# n64rgb.net
KiCad netlist of a schematic drawn in EAGLE
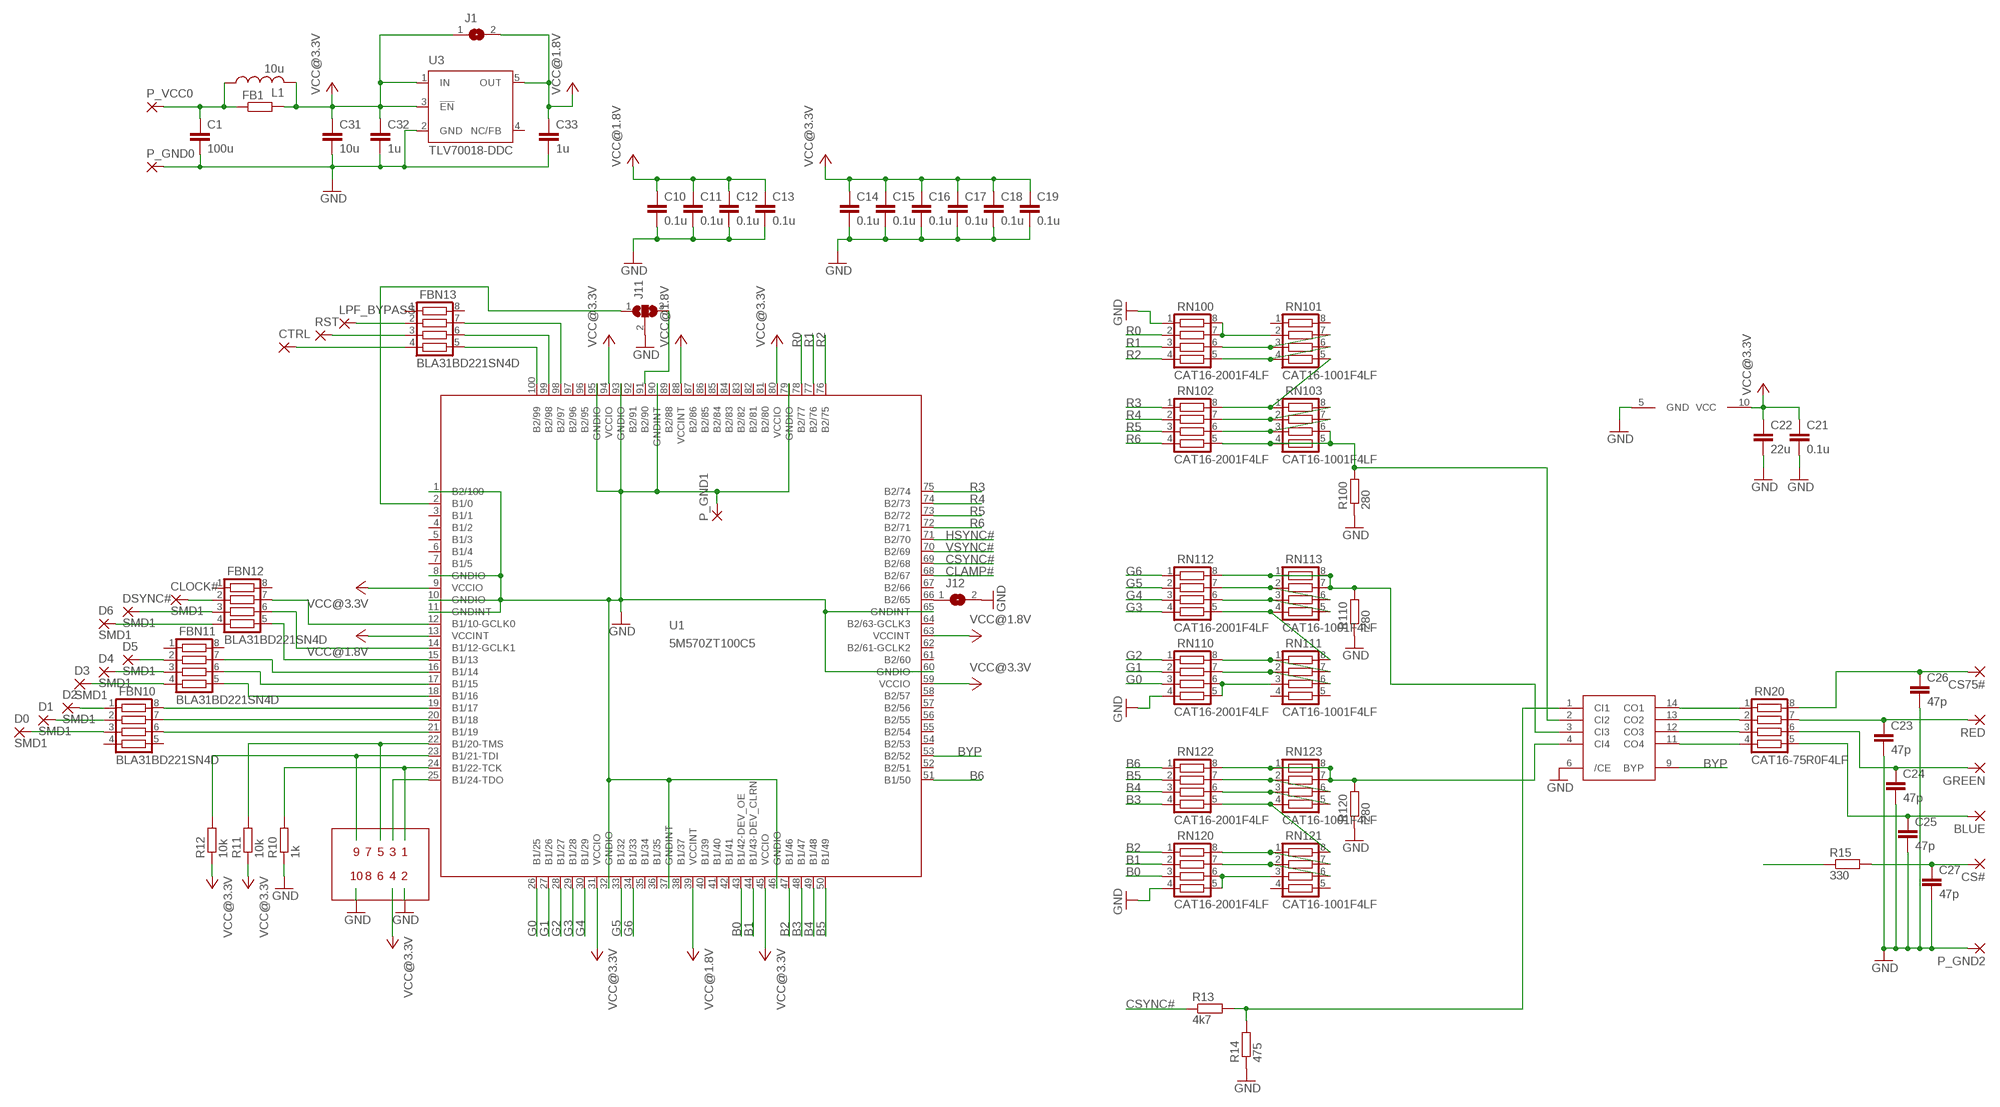
[diagram p0: schematic, sheet 1]

(export (version "E")
  (design (tool "Eeschema 10.0.6"))
  (components
    (comp (ref "BLUE")
      (value "SMD2")
      (footprint "eagle-import:SMD1,27-2,54")
      (libsource (lib "eagle-import") (part "SMD2"))
    )
    (comp (ref "C1")
      (value "100u")
      (footprint "eagle-import:C1206K")
      (libsource (lib "eagle-import") (part "C-EUC1206K"))
    )
    (comp (ref "C10")
      (value "0.1u")
      (footprint "eagle-import:C0603")
      (libsource (lib "eagle-import") (part "C-EUC0603"))
    )
    (comp (ref "C11")
      (value "0.1u")
      (footprint "eagle-import:C0603")
      (libsource (lib "eagle-import") (part "C-EUC0603"))
    )
    (comp (ref "C12")
      (value "0.1u")
      (footprint "eagle-import:C0603")
      (libsource (lib "eagle-import") (part "C-EUC0603"))
    )
    (comp (ref "C13")
      (value "0.1u")
      (footprint "eagle-import:C0603")
      (libsource (lib "eagle-import") (part "C-EUC0603"))
    )
    (comp (ref "C14")
      (value "0.1u")
      (footprint "eagle-import:C0603")
      (libsource (lib "eagle-import") (part "C-EUC0603"))
    )
    (comp (ref "C15")
      (value "0.1u")
      (footprint "eagle-import:C0603")
      (libsource (lib "eagle-import") (part "C-EUC0603"))
    )
    (comp (ref "C16")
      (value "0.1u")
      (footprint "eagle-import:C0603")
      (libsource (lib "eagle-import") (part "C-EUC0603"))
    )
    (comp (ref "C17")
      (value "0.1u")
      (footprint "eagle-import:C0603")
      (libsource (lib "eagle-import") (part "C-EUC0603"))
    )
    (comp (ref "C18")
      (value "0.1u")
      (footprint "eagle-import:C0603")
      (libsource (lib "eagle-import") (part "C-EUC0603"))
    )
    (comp (ref "C19")
      (value "0.1u")
      (footprint "eagle-import:C0603")
      (libsource (lib "eagle-import") (part "C-EUC0603"))
    )
    (comp (ref "C21")
      (value "0.1u")
      (footprint "eagle-import:C0603")
      (libsource (lib "eagle-import") (part "C-EUC0603"))
    )
    (comp (ref "C22")
      (value "22u")
      (footprint "eagle-import:C1206K")
      (libsource (lib "eagle-import") (part "C-EUC1206K"))
    )
    (comp (ref "C23")
      (value "47p")
      (footprint "eagle-import:C0603")
      (libsource (lib "eagle-import") (part "C-EUC0603"))
    )
    (comp (ref "C24")
      (value "47p")
      (footprint "eagle-import:C0603")
      (libsource (lib "eagle-import") (part "C-EUC0603"))
    )
    (comp (ref "C25")
      (value "47p")
      (footprint "eagle-import:C0603")
      (libsource (lib "eagle-import") (part "C-EUC0603"))
    )
    (comp (ref "C26")
      (value "47p")
      (footprint "eagle-import:C0603")
      (libsource (lib "eagle-import") (part "C-EUC0603"))
    )
    (comp (ref "C27")
      (value "47p")
      (footprint "eagle-import:C0603")
      (libsource (lib "eagle-import") (part "C-EUC0603"))
    )
    (comp (ref "C31")
      (value "10u")
      (footprint "eagle-import:C1206K")
      (libsource (lib "eagle-import") (part "C-EUC1206K"))
    )
    (comp (ref "C32")
      (value "1u")
      (footprint "eagle-import:C0603")
      (libsource (lib "eagle-import") (part "C-EUC0603"))
    )
    (comp (ref "C33")
      (value "1u")
      (footprint "eagle-import:C0603")
      (libsource (lib "eagle-import") (part "C-EUC0603"))
    )
    (comp (ref "CLOCK#")
      (value "SMD1")
      (footprint "eagle-import:SMD0,8-1,6")
      (libsource (lib "eagle-import") (part "SMD1"))
    )
    (comp (ref "CS#")
      (value "SMD2")
      (footprint "eagle-import:SMD1,27-2,54")
      (libsource (lib "eagle-import") (part "SMD2"))
    )
    (comp (ref "CS75#")
      (value "SMD2")
      (footprint "eagle-import:SMD1,27-2,54")
      (libsource (lib "eagle-import") (part "SMD2"))
    )
    (comp (ref "CTRL")
      (value "SMD2")
      (footprint "eagle-import:SMD1,27-2,54")
      (libsource (lib "eagle-import") (part "SMD2"))
    )
    (comp (ref "D0")
      (value "SMD1")
      (footprint "eagle-import:SMD0,8-1,6")
      (libsource (lib "eagle-import") (part "SMD1"))
    )
    (comp (ref "D1")
      (value "SMD1")
      (footprint "eagle-import:SMD0,8-1,6")
      (libsource (lib "eagle-import") (part "SMD1"))
    )
    (comp (ref "D2")
      (value "SMD1")
      (footprint "eagle-import:SMD0,8-1,6")
      (libsource (lib "eagle-import") (part "SMD1"))
    )
    (comp (ref "D3")
      (value "SMD1")
      (footprint "eagle-import:SMD0,8-1,6")
      (libsource (lib "eagle-import") (part "SMD1"))
    )
    (comp (ref "D4")
      (value "SMD1")
      (footprint "eagle-import:SMD0,8-1,6")
      (libsource (lib "eagle-import") (part "SMD1"))
    )
    (comp (ref "D5")
      (value "SMD1")
      (footprint "eagle-import:SMD0,8-1,6")
      (libsource (lib "eagle-import") (part "SMD1"))
    )
    (comp (ref "D6")
      (value "SMD1")
      (footprint "eagle-import:SMD0,8-1,6")
      (libsource (lib "eagle-import") (part "SMD1"))
    )
    (comp (ref "DSYNC#")
      (value "SMD1")
      (footprint "eagle-import:SMD0,8-1,6")
      (libsource (lib "eagle-import") (part "SMD1"))
    )
    (comp (ref "FB1")
      (value "R-EU_R0603")
      (footprint "eagle-import:R0603")
      (libsource (lib "eagle-import") (part "R-EU_R0603"))
    )
    (comp (ref "FBN10")
      (value "BLA31BD221SN4D")
      (footprint "eagle-import:CTS742C083")
      (libsource (lib "eagle-import") (part "CTS742C083"))
    )
    (comp (ref "FBN11")
      (value "BLA31BD221SN4D")
      (footprint "eagle-import:CTS742C083")
      (libsource (lib "eagle-import") (part "CTS742C083"))
    )
    (comp (ref "FBN12")
      (value "BLA31BD221SN4D")
      (footprint "eagle-import:CTS742C083")
      (libsource (lib "eagle-import") (part "CTS742C083"))
    )
    (comp (ref "FBN13")
      (value "BLA31BD221SN4D")
      (footprint "eagle-import:CTS742C083")
      (libsource (lib "eagle-import") (part "CTS742C083"))
    )
    (comp (ref "GREEN")
      (value "SMD2")
      (footprint "eagle-import:SMD1,27-2,54")
      (libsource (lib "eagle-import") (part "SMD2"))
    )
    (comp (ref "J1") (value "SJ") (footprint "eagle-import:SJ") (libsource (lib "eagle-import") (part "SJ")))
    (comp (ref "J11")
      (value "SJ2W")
      (footprint "eagle-import:SJ_2")
      (libsource (lib "eagle-import") (part "SJ2W"))
    )
    (comp (ref "J12") (value "SJ") (footprint "eagle-import:SJ") (libsource (lib "eagle-import") (part "SJ")))
    (comp (ref "L1")
      (value "10u")
      (footprint "eagle-import:L3230M")
      (libsource (lib "eagle-import") (part "L-USL3230M"))
    )
    (comp (ref "LPF_BYPASS")
      (value "SMD2")
      (footprint "eagle-import:SMD1,27-2,54")
      (libsource (lib "eagle-import") (part "SMD2"))
    )
    (comp (ref "P_GND0")
      (value "SMD2")
      (footprint "eagle-import:SMD1,27-2,54")
      (libsource (lib "eagle-import") (part "SMD2"))
    )
    (comp (ref "P_GND1")
      (value "SMD2")
      (footprint "eagle-import:SMD1,27-2,54")
      (libsource (lib "eagle-import") (part "SMD2"))
    )
    (comp (ref "P_GND2")
      (value "SMD2")
      (footprint "eagle-import:SMD1,27-2,54")
      (libsource (lib "eagle-import") (part "SMD2"))
    )
    (comp (ref "P_VCC0")
      (value "SMD2")
      (footprint "eagle-import:SMD1,27-2,54")
      (libsource (lib "eagle-import") (part "SMD2"))
    )
    (comp (ref "R10")
      (value "1k")
      (footprint "eagle-import:R0603")
      (libsource (lib "eagle-import") (part "R-EU_R0603"))
    )
    (comp (ref "R11")
      (value "10k")
      (footprint "eagle-import:R0603")
      (libsource (lib "eagle-import") (part "R-EU_R0603"))
    )
    (comp (ref "R12")
      (value "10k")
      (footprint "eagle-import:R0603")
      (libsource (lib "eagle-import") (part "R-EU_R0603"))
    )
    (comp (ref "R13")
      (value "4k7")
      (footprint "eagle-import:R0603")
      (libsource (lib "eagle-import") (part "R-EU_R0603"))
    )
    (comp (ref "R14")
      (value "475")
      (footprint "eagle-import:R0603")
      (libsource (lib "eagle-import") (part "R-EU_R0603"))
    )
    (comp (ref "R15")
      (value "330")
      (footprint "eagle-import:R0603")
      (libsource (lib "eagle-import") (part "R-EU_R0603"))
    )
    (comp (ref "R100")
      (value "280")
      (footprint "eagle-import:R0603")
      (libsource (lib "eagle-import") (part "R-EU_R0603"))
    )
    (comp (ref "R110")
      (value "280")
      (footprint "eagle-import:R0603")
      (libsource (lib "eagle-import") (part "R-EU_R0603"))
    )
    (comp (ref "R120")
      (value "280")
      (footprint "eagle-import:R0603")
      (libsource (lib "eagle-import") (part "R-EU_R0603"))
    )
    (comp (ref "RED")
      (value "SMD2")
      (footprint "eagle-import:SMD1,27-2,54")
      (libsource (lib "eagle-import") (part "SMD2"))
    )
    (comp (ref "RN20")
      (value "CAT16-75R0F4LF")
      (footprint "eagle-import:CTS742C083")
      (libsource (lib "eagle-import") (part "CTS742C083"))
    )
    (comp (ref "RN100")
      (value "CAT16-2001F4LF")
      (footprint "eagle-import:CTS742C083")
      (libsource (lib "eagle-import") (part "CTS742C083"))
    )
    (comp (ref "RN101")
      (value "CAT16-1001F4LF")
      (footprint "eagle-import:CTS742C083")
      (libsource (lib "eagle-import") (part "CTS742C083"))
    )
    (comp (ref "RN102")
      (value "CAT16-2001F4LF")
      (footprint "eagle-import:CTS742C083")
      (libsource (lib "eagle-import") (part "CTS742C083"))
    )
    (comp (ref "RN103")
      (value "CAT16-1001F4LF")
      (footprint "eagle-import:CTS742C083")
      (libsource (lib "eagle-import") (part "CTS742C083"))
    )
    (comp (ref "RN110")
      (value "CAT16-2001F4LF")
      (footprint "eagle-import:CTS742C083")
      (libsource (lib "eagle-import") (part "CTS742C083"))
    )
    (comp (ref "RN111")
      (value "CAT16-1001F4LF")
      (footprint "eagle-import:CTS742C083")
      (libsource (lib "eagle-import") (part "CTS742C083"))
    )
    (comp (ref "RN112")
      (value "CAT16-2001F4LF")
      (footprint "eagle-import:CTS742C083")
      (libsource (lib "eagle-import") (part "CTS742C083"))
    )
    (comp (ref "RN113")
      (value "CAT16-1001F4LF")
      (footprint "eagle-import:CTS742C083")
      (libsource (lib "eagle-import") (part "CTS742C083"))
    )
    (comp (ref "RN120")
      (value "CAT16-2001F4LF")
      (footprint "eagle-import:CTS742C083")
      (libsource (lib "eagle-import") (part "CTS742C083"))
    )
    (comp (ref "RN121")
      (value "CAT16-1001F4LF")
      (footprint "eagle-import:CTS742C083")
      (libsource (lib "eagle-import") (part "CTS742C083"))
    )
    (comp (ref "RN122")
      (value "CAT16-2001F4LF")
      (footprint "eagle-import:CTS742C083")
      (libsource (lib "eagle-import") (part "CTS742C083"))
    )
    (comp (ref "RN123")
      (value "CAT16-1001F4LF")
      (footprint "eagle-import:CTS742C083")
      (libsource (lib "eagle-import") (part "CTS742C083"))
    )
    (comp (ref "RST")
      (value "SMD2")
      (footprint "eagle-import:SMD1,27-2,54")
      (libsource (lib "eagle-import") (part "SMD2"))
    )
    (comp (ref "U1")
      (value "5M570ZT100C5")
      (footprint "eagle-import:TQFP100")
      (libsource (lib "eagle-import") (part "5M570ZT100C5"))
    )
    (comp (ref "U2")
      (value "THS7374")
      (footprint "eagle-import:THS7374")
      (libsource (lib "eagle-import") (part "THS7374"))
    )
    (comp (ref "U3")
      (value "TLV70018-DDC")
      (footprint "eagle-import:SOT23-DBV")
      (fields (field (name "MF") "TEXAS INSTRUMENT CONNECTORS") (field (name "MPN") "TPS77018DBVR"))
      (libsource (lib "eagle-import") (part "TPS77018"))
    )
  )
  (nets
    (net (code "1") (name "/B0") (class "Default")
      (node (ref "RN120") (pin "3") (pinfunction "3_3") (pintype "passive"))
      (node (ref "U1") (pin "43") (pinfunction "B1/42-DEV_OE_43") (pintype "bidirectional"))
    )
    (net (code "2") (name "/B1") (class "Default")
      (node (ref "RN120") (pin "2") (pinfunction "2_2") (pintype "passive"))
      (node (ref "U1") (pin "44") (pinfunction "B1/43-DEV_CLRN_44") (pintype "bidirectional"))
    )
    (net (code "3") (name "/B2") (class "Default")
      (node (ref "RN120") (pin "1") (pinfunction "1_1") (pintype "passive"))
      (node (ref "U1") (pin "47") (pinfunction "B1/46_47") (pintype "bidirectional"))
    )
    (net (code "4") (name "/B3") (class "Default")
      (node (ref "RN122") (pin "4") (pinfunction "4_4") (pintype "passive"))
      (node (ref "U1") (pin "48") (pinfunction "B1/47_48") (pintype "bidirectional"))
    )
    (net (code "5") (name "/B4") (class "Default")
      (node (ref "RN122") (pin "3") (pinfunction "3_3") (pintype "passive"))
      (node (ref "U1") (pin "49") (pinfunction "B1/48_49") (pintype "bidirectional"))
    )
    (net (code "6") (name "/B5") (class "Default")
      (node (ref "RN122") (pin "2") (pinfunction "2_2") (pintype "passive"))
      (node (ref "U1") (pin "50") (pinfunction "B1/49_50") (pintype "bidirectional"))
    )
    (net (code "7") (name "/B6") (class "Default")
      (node (ref "RN122") (pin "1") (pinfunction "1_1") (pintype "passive"))
      (node (ref "U1") (pin "51") (pinfunction "B1/50_51") (pintype "bidirectional"))
    )
    (net (code "8") (name "/BYP") (class "Default")
      (node (ref "U1") (pin "53") (pinfunction "B2/52_53") (pintype "bidirectional"))
      (node (ref "U2") (pin "9") (pinfunction "BYP_9") (pintype "bidirectional"))
    )
    (net (code "9") (name "/CLAMP#") (class "Default")
      (node (ref "U1") (pin "68") (pinfunction "B2/67_68") (pintype "bidirectional"))
    )
    (net (code "10") (name "/CSYNC#") (class "Default")
      (node (ref "R13") (pin "1") (pinfunction "1_1") (pintype "passive"))
      (node (ref "R15") (pin "1") (pinfunction "1_1") (pintype "passive"))
      (node (ref "U1") (pin "69") (pinfunction "B2/68_69") (pintype "bidirectional"))
    )
    (net (code "11") (name "/G0") (class "Default")
      (node (ref "RN110") (pin "3") (pinfunction "3_3") (pintype "passive"))
      (node (ref "U1") (pin "26") (pinfunction "B1/25_26") (pintype "bidirectional"))
    )
    (net (code "12") (name "/G1") (class "Default")
      (node (ref "RN110") (pin "2") (pinfunction "2_2") (pintype "passive"))
      (node (ref "U1") (pin "27") (pinfunction "B1/26_27") (pintype "bidirectional"))
    )
    (net (code "13") (name "/G2") (class "Default")
      (node (ref "RN110") (pin "1") (pinfunction "1_1") (pintype "passive"))
      (node (ref "U1") (pin "28") (pinfunction "B1/27_28") (pintype "bidirectional"))
    )
    (net (code "14") (name "/G3") (class "Default")
      (node (ref "RN112") (pin "4") (pinfunction "4_4") (pintype "passive"))
      (node (ref "U1") (pin "29") (pinfunction "B1/28_29") (pintype "bidirectional"))
    )
    (net (code "15") (name "/G4") (class "Default")
      (node (ref "RN112") (pin "3") (pinfunction "3_3") (pintype "passive"))
      (node (ref "U1") (pin "30") (pinfunction "B1/29_30") (pintype "bidirectional"))
    )
    (net (code "16") (name "/G5") (class "Default")
      (node (ref "RN112") (pin "2") (pinfunction "2_2") (pintype "passive"))
      (node (ref "U1") (pin "33") (pinfunction "B1/32_33") (pintype "bidirectional"))
    )
    (net (code "17") (name "/G6") (class "Default")
      (node (ref "RN112") (pin "1") (pinfunction "1_1") (pintype "passive"))
      (node (ref "U1") (pin "34") (pinfunction "B1/33_34") (pintype "bidirectional"))
    )
    (net (code "18") (name "/HSYNC#") (class "Default")
      (node (ref "U1") (pin "71") (pinfunction "B2/70_71") (pintype "bidirectional"))
    )
    (net (code "19") (name "/R0") (class "Default")
      (node (ref "RN100") (pin "2") (pinfunction "2_2") (pintype "passive"))
      (node (ref "U1") (pin "78") (pinfunction "B2/77_78") (pintype "bidirectional"))
    )
    (net (code "20") (name "/R1") (class "Default")
      (node (ref "RN100") (pin "3") (pinfunction "3_3") (pintype "passive"))
      (node (ref "U1") (pin "77") (pinfunction "B2/76_77") (pintype "bidirectional"))
    )
    (net (code "21") (name "/R2") (class "Default")
      (node (ref "RN100") (pin "4") (pinfunction "4_4") (pintype "passive"))
      (node (ref "U1") (pin "76") (pinfunction "B2/75_76") (pintype "bidirectional"))
    )
    (net (code "22") (name "/R3") (class "Default")
      (node (ref "RN102") (pin "1") (pinfunction "1_1") (pintype "passive"))
      (node (ref "U1") (pin "75") (pinfunction "B2/74_75") (pintype "bidirectional"))
    )
    (net (code "23") (name "/R4") (class "Default")
      (node (ref "RN102") (pin "2") (pinfunction "2_2") (pintype "passive"))
      (node (ref "U1") (pin "74") (pinfunction "B2/73_74") (pintype "bidirectional"))
    )
    (net (code "24") (name "/R5") (class "Default")
      (node (ref "RN102") (pin "3") (pinfunction "3_3") (pintype "passive"))
      (node (ref "U1") (pin "73") (pinfunction "B2/72_73") (pintype "bidirectional"))
    )
    (net (code "25") (name "/R6") (class "Default")
      (node (ref "RN102") (pin "4") (pinfunction "4_4") (pintype "passive"))
      (node (ref "U1") (pin "72") (pinfunction "B2/71_72") (pintype "bidirectional"))
    )
    (net (code "26") (name "/VSYNC#") (class "Default")
      (node (ref "U1") (pin "70") (pinfunction "B2/69_70") (pintype "bidirectional"))
    )
    (net (code "27") (name "GND") (class "Default")
      (node (ref "C1") (pin "2") (pinfunction "2_2") (pintype "passive"))
      (node (ref "C10") (pin "2") (pinfunction "2_2") (pintype "passive"))
      (node (ref "C11") (pin "2") (pinfunction "2_2") (pintype "passive"))
      (node (ref "C12") (pin "2") (pinfunction "2_2") (pintype "passive"))
      (node (ref "C13") (pin "2") (pinfunction "2_2") (pintype "passive"))
      (node (ref "C14") (pin "2") (pinfunction "2_2") (pintype "passive"))
      (node (ref "C15") (pin "2") (pinfunction "2_2") (pintype "passive"))
      (node (ref "C16") (pin "2") (pinfunction "2_2") (pintype "passive"))
      (node (ref "C17") (pin "2") (pinfunction "2_2") (pintype "passive"))
      (node (ref "C18") (pin "2") (pinfunction "2_2") (pintype "passive"))
      (node (ref "C19") (pin "2") (pinfunction "2_2") (pintype "passive"))
      (node (ref "C21") (pin "2") (pinfunction "2_2") (pintype "passive"))
      (node (ref "C22") (pin "2") (pinfunction "2_2") (pintype "passive"))
      (node (ref "C23") (pin "2") (pinfunction "2_2") (pintype "passive"))
      (node (ref "C24") (pin "2") (pinfunction "2_2") (pintype "passive"))
      (node (ref "C25") (pin "2") (pinfunction "2_2") (pintype "passive"))
      (node (ref "C26") (pin "2") (pinfunction "2_2") (pintype "passive"))
      (node (ref "C27") (pin "2") (pinfunction "2_2") (pintype "passive"))
      (node (ref "C31") (pin "2") (pinfunction "2_2") (pintype "passive"))
      (node (ref "C32") (pin "2") (pinfunction "2_2") (pintype "passive"))
      (node (ref "C33") (pin "2") (pinfunction "2_2") (pintype "passive"))
      (node (ref "J11") (pin "2") (pinfunction "2_2") (pintype "passive"))
      (node (ref "J12") (pin "2") (pinfunction "2_2") (pintype "passive"))
      (node (ref "P_GND0") (pin "1") (pinfunction "P_1") (pintype "passive"))
      (node (ref "P_GND1") (pin "1") (pinfunction "P_1") (pintype "passive"))
      (node (ref "P_GND2") (pin "1") (pinfunction "P_1") (pintype "passive"))
      (node (ref "R10") (pin "1") (pinfunction "1_1") (pintype "passive"))
      (node (ref "R100") (pin "1") (pinfunction "1_1") (pintype "passive"))
      (node (ref "R110") (pin "1") (pinfunction "1_1") (pintype "passive"))
      (node (ref "R120") (pin "1") (pinfunction "1_1") (pintype "passive"))
      (node (ref "R14") (pin "1") (pinfunction "1_1") (pintype "passive"))
      (node (ref "RN100") (pin "1") (pinfunction "1_1") (pintype "passive"))
      (node (ref "RN110") (pin "4") (pinfunction "4_4") (pintype "passive"))
      (node (ref "RN120") (pin "4") (pinfunction "4_4") (pintype "passive"))
      (node (ref "U1") (pin "1") (pinfunction "B2/100_1") (pintype "bidirectional"))
      (node (ref "U1") (pin "10") (pinfunction "GNDIO_10") (pintype "power_in"))
      (node (ref "U1") (pin "11") (pinfunction "GNDINT_11") (pintype "power_in"))
      (node (ref "U1") (pin "32") (pinfunction "GNDIO_32") (pintype "power_in"))
      (node (ref "U1") (pin "37") (pinfunction "GNDINT_37") (pintype "power_in"))
      (node (ref "U1") (pin "46") (pinfunction "GNDIO_46") (pintype "power_in"))
      (node (ref "U1") (pin "60") (pinfunction "GNDIO_60") (pintype "power_in"))
      (node (ref "U1") (pin "65") (pinfunction "GNDINT_65") (pintype "power_in"))
      (node (ref "U1") (pin "79") (pinfunction "GNDIO_79") (pintype "power_in"))
      (node (ref "U1") (pin "8") (pinfunction "GNDIO_8") (pintype "power_in"))
      (node (ref "U1") (pin "90") (pinfunction "GNDINT_90") (pintype "power_in"))
      (node (ref "U1") (pin "93") (pinfunction "GNDIO_93") (pintype "power_in"))
      (node (ref "U1") (pin "95") (pinfunction "GNDIO_95") (pintype "power_in"))
      (node (ref "U2") (pin "5") (pinfunction "GND_5") (pintype "bidirectional"))
      (node (ref "U2") (pin "6") (pinfunction "/CE_6") (pintype "bidirectional"))
      (node (ref "U3") (pin "2") (pinfunction "GND_2") (pintype "power_in"))
    )
    (net (code "28") (name "Net-(BLUE-P)") (class "Default")
      (node (ref "BLUE") (pin "1") (pinfunction "P_1") (pintype "passive"))
      (node (ref "C25") (pin "1") (pinfunction "1_1") (pintype "passive"))
      (node (ref "RN20") (pin "5") (pinfunction "5_5") (pintype "passive"))
    )
    (net (code "29") (name "Net-(CLOCK#-P)") (class "Default")
      (node (ref "CLOCK#") (pin "P$1") (pinfunction "P_P$1") (pintype "passive"))
      (node (ref "FBN12") (pin "2") (pinfunction "2_2") (pintype "passive"))
    )
    (net (code "30") (name "Net-(CS#-P)") (class "Default")
      (node (ref "C27") (pin "1") (pinfunction "1_1") (pintype "passive"))
      (node (ref "CS#") (pin "1") (pinfunction "P_1") (pintype "passive"))
      (node (ref "R15") (pin "2") (pinfunction "2_2") (pintype "passive"))
    )
    (net (code "31") (name "Net-(CS75#-P)") (class "Default")
      (node (ref "C26") (pin "1") (pinfunction "1_1") (pintype "passive"))
      (node (ref "CS75#") (pin "1") (pinfunction "P_1") (pintype "passive"))
      (node (ref "RN20") (pin "8") (pinfunction "8_8") (pintype "passive"))
    )
    (net (code "32") (name "Net-(CTRL-P)") (class "Default")
      (node (ref "CTRL") (pin "1") (pinfunction "P_1") (pintype "passive"))
      (node (ref "FBN13") (pin "4") (pinfunction "4_4") (pintype "passive"))
    )
    (net (code "33") (name "Net-(D0-P)") (class "Default")
      (node (ref "D0") (pin "P$1") (pinfunction "P_P$1") (pintype "passive"))
      (node (ref "FBN10") (pin "3") (pinfunction "3_3") (pintype "passive"))
    )
    (net (code "34") (name "Net-(D1-P)") (class "Default")
      (node (ref "D1") (pin "P$1") (pinfunction "P_P$1") (pintype "passive"))
      (node (ref "FBN10") (pin "2") (pinfunction "2_2") (pintype "passive"))
    )
    (net (code "35") (name "Net-(D2-P)") (class "Default")
      (node (ref "D2") (pin "P$1") (pinfunction "P_P$1") (pintype "passive"))
      (node (ref "FBN10") (pin "1") (pinfunction "1_1") (pintype "passive"))
    )
    (net (code "36") (name "Net-(D3-P)") (class "Default")
      (node (ref "D3") (pin "P$1") (pinfunction "P_P$1") (pintype "passive"))
      (node (ref "FBN11") (pin "4") (pinfunction "4_4") (pintype "passive"))
    )
    (net (code "37") (name "Net-(D4-P)") (class "Default")
      (node (ref "D4") (pin "P$1") (pinfunction "P_P$1") (pintype "passive"))
      (node (ref "FBN11") (pin "3") (pinfunction "3_3") (pintype "passive"))
    )
    (net (code "38") (name "Net-(D5-P)") (class "Default")
      (node (ref "D5") (pin "P$1") (pinfunction "P_P$1") (pintype "passive"))
      (node (ref "FBN11") (pin "2") (pinfunction "2_2") (pintype "passive"))
    )
    (net (code "39") (name "Net-(D6-P)") (class "Default")
      (node (ref "D6") (pin "P$1") (pinfunction "P_P$1") (pintype "passive"))
      (node (ref "FBN12") (pin "4") (pinfunction "4_4") (pintype "passive"))
    )
    (net (code "40") (name "Net-(DSYNC#-P)") (class "Default")
      (node (ref "DSYNC#") (pin "P$1") (pinfunction "P_P$1") (pintype "passive"))
      (node (ref "FBN12") (pin "3") (pinfunction "3_3") (pintype "passive"))
    )
    (net (code "41") (name "Net-(GREEN-P)") (class "Default")
      (node (ref "C24") (pin "1") (pinfunction "1_1") (pintype "passive"))
      (node (ref "GREEN") (pin "1") (pinfunction "P_1") (pintype "passive"))
      (node (ref "RN20") (pin "6") (pinfunction "6_6") (pintype "passive"))
    )
    (net (code "42") (name "Net-(LPF_BYPASS-P)") (class "Default")
      (node (ref "FBN13") (pin "2") (pinfunction "2_2") (pintype "passive"))
      (node (ref "LPF_BYPASS") (pin "1") (pinfunction "P_1") (pintype "passive"))
    )
    (net (code "43") (name "Net-(P_VCC0-P)") (class "Default")
      (node (ref "C1") (pin "1") (pinfunction "1_1") (pintype "passive"))
      (node (ref "FB1") (pin "1") (pinfunction "1_1") (pintype "passive"))
      (node (ref "L1") (pin "1") (pinfunction "1_1") (pintype "passive"))
      (node (ref "P_VCC0") (pin "1") (pinfunction "P_1") (pintype "passive"))
    )
    (net (code "44") (name "Net-(RED-P)") (class "Default")
      (node (ref "C23") (pin "1") (pinfunction "1_1") (pintype "passive"))
      (node (ref "RED") (pin "1") (pinfunction "P_1") (pintype "passive"))
      (node (ref "RN20") (pin "7") (pinfunction "7_7") (pintype "passive"))
    )
    (net (code "45") (name "Net-(RN100-Pad5)") (class "Default")
      (node (ref "RN100") (pin "5") (pinfunction "5_5") (pintype "passive"))
      (node (ref "RN101") (pin "4") (pinfunction "4_4") (pintype "passive"))
      (node (ref "RN101") (pin "6") (pinfunction "6_6") (pintype "passive"))
    )
    (net (code "46") (name "Net-(RN100-Pad6)") (class "Default")
      (node (ref "RN100") (pin "6") (pinfunction "6_6") (pintype "passive"))
      (node (ref "RN101") (pin "3") (pinfunction "3_3") (pintype "passive"))
      (node (ref "RN101") (pin "7") (pinfunction "7_7") (pintype "passive"))
    )
    (net (code "47") (name "Net-(RN100-Pad7)") (class "Default")
      (node (ref "RN100") (pin "7") (pinfunction "7_7") (pintype "passive"))
      (node (ref "RN100") (pin "8") (pinfunction "8_8") (pintype "passive"))
      (node (ref "RN101") (pin "2") (pinfunction "2_2") (pintype "passive"))
    )
    (net (code "48") (name "Net-(RN101-Pad5)") (class "Default")
      (node (ref "RN101") (pin "5") (pinfunction "5_5") (pintype "passive"))
      (node (ref "RN102") (pin "8") (pinfunction "8_8") (pintype "passive"))
      (node (ref "RN103") (pin "1") (pinfunction "1_1") (pintype "passive"))
    )
    (net (code "49") (name "Net-(RN102-Pad6)") (class "Default")
      (node (ref "RN102") (pin "6") (pinfunction "6_6") (pintype "passive"))
      (node (ref "RN103") (pin "3") (pinfunction "3_3") (pintype "passive"))
      (node (ref "RN103") (pin "7") (pinfunction "7_7") (pintype "passive"))
    )
    (net (code "50") (name "Net-(RN102-Pad7)") (class "Default")
      (node (ref "RN102") (pin "7") (pinfunction "7_7") (pintype "passive"))
      (node (ref "RN103") (pin "2") (pinfunction "2_2") (pintype "passive"))
      (node (ref "RN103") (pin "8") (pinfunction "8_8") (pintype "passive"))
    )
    (net (code "51") (name "Net-(RN110-Pad5)") (class "Default")
      (node (ref "RN110") (pin "5") (pinfunction "5_5") (pintype "passive"))
      (node (ref "RN110") (pin "6") (pinfunction "6_6") (pintype "passive"))
      (node (ref "RN111") (pin "3") (pinfunction "3_3") (pintype "passive"))
    )
    (net (code "52") (name "Net-(RN110-Pad7)") (class "Default")
      (node (ref "RN110") (pin "7") (pinfunction "7_7") (pintype "passive"))
      (node (ref "RN111") (pin "2") (pinfunction "2_2") (pintype "passive"))
      (node (ref "RN111") (pin "6") (pinfunction "6_6") (pintype "passive"))
    )
    (net (code "53") (name "Net-(RN110-Pad8)") (class "Default")
      (node (ref "RN110") (pin "8") (pinfunction "8_8") (pintype "passive"))
      (node (ref "RN111") (pin "1") (pinfunction "1_1") (pintype "passive"))
      (node (ref "RN111") (pin "7") (pinfunction "7_7") (pintype "passive"))
    )
    (net (code "54") (name "Net-(RN111-Pad8)") (class "Default")
      (node (ref "RN111") (pin "8") (pinfunction "8_8") (pintype "passive"))
      (node (ref "RN112") (pin "5") (pinfunction "5_5") (pintype "passive"))
      (node (ref "RN113") (pin "4") (pinfunction "4_4") (pintype "passive"))
    )
    (net (code "55") (name "Net-(RN112-Pad6)") (class "Default")
      (node (ref "RN112") (pin "6") (pinfunction "6_6") (pintype "passive"))
      (node (ref "RN113") (pin "3") (pinfunction "3_3") (pintype "passive"))
      (node (ref "RN113") (pin "5") (pinfunction "5_5") (pintype "passive"))
    )
    (net (code "56") (name "Net-(RN112-Pad7)") (class "Default")
      (node (ref "RN112") (pin "7") (pinfunction "7_7") (pintype "passive"))
      (node (ref "RN113") (pin "2") (pinfunction "2_2") (pintype "passive"))
      (node (ref "RN113") (pin "6") (pinfunction "6_6") (pintype "passive"))
    )
    (net (code "57") (name "Net-(RN120-Pad5)") (class "Default")
      (node (ref "RN120") (pin "5") (pinfunction "5_5") (pintype "passive"))
      (node (ref "RN120") (pin "6") (pinfunction "6_6") (pintype "passive"))
      (node (ref "RN121") (pin "3") (pinfunction "3_3") (pintype "passive"))
    )
    (net (code "58") (name "Net-(RN120-Pad7)") (class "Default")
      (node (ref "RN120") (pin "7") (pinfunction "7_7") (pintype "passive"))
      (node (ref "RN121") (pin "2") (pinfunction "2_2") (pintype "passive"))
      (node (ref "RN121") (pin "6") (pinfunction "6_6") (pintype "passive"))
    )
    (net (code "59") (name "Net-(RN120-Pad8)") (class "Default")
      (node (ref "RN120") (pin "8") (pinfunction "8_8") (pintype "passive"))
      (node (ref "RN121") (pin "1") (pinfunction "1_1") (pintype "passive"))
      (node (ref "RN121") (pin "7") (pinfunction "7_7") (pintype "passive"))
    )
    (net (code "60") (name "Net-(RN121-Pad8)") (class "Default")
      (node (ref "RN121") (pin "8") (pinfunction "8_8") (pintype "passive"))
      (node (ref "RN122") (pin "5") (pinfunction "5_5") (pintype "passive"))
      (node (ref "RN123") (pin "4") (pinfunction "4_4") (pintype "passive"))
    )
    (net (code "61") (name "Net-(RN122-Pad6)") (class "Default")
      (node (ref "RN122") (pin "6") (pinfunction "6_6") (pintype "passive"))
      (node (ref "RN123") (pin "3") (pinfunction "3_3") (pintype "passive"))
      (node (ref "RN123") (pin "5") (pinfunction "5_5") (pintype "passive"))
    )
    (net (code "62") (name "Net-(RN122-Pad7)") (class "Default")
      (node (ref "RN122") (pin "7") (pinfunction "7_7") (pintype "passive"))
      (node (ref "RN123") (pin "2") (pinfunction "2_2") (pintype "passive"))
      (node (ref "RN123") (pin "6") (pinfunction "6_6") (pintype "passive"))
    )
    (net (code "63") (name "Net-(RST-P)") (class "Default")
      (node (ref "FBN13") (pin "3") (pinfunction "3_3") (pintype "passive"))
      (node (ref "RST") (pin "1") (pinfunction "P_1") (pintype "passive"))
    )
    (net (code "64") (name "Net-(U1-B1{slash}0)") (class "Default")
      (node (ref "J11") (pin "1") (pinfunction "1_1") (pintype "passive"))
      (node (ref "U1") (pin "2") (pinfunction "B1/0_2") (pintype "bidirectional"))
    )
    (net (code "65") (name "Net-(U1-B1{slash}10-GCLK0)") (class "Default")
      (node (ref "FBN12") (pin "7") (pinfunction "7_7") (pintype "passive"))
      (node (ref "U1") (pin "12") (pinfunction "B1/10-GCLK0_12") (pintype "bidirectional"))
    )
    (net (code "66") (name "Net-(U1-B1{slash}12-GCLK1)") (class "Default")
      (node (ref "FBN12") (pin "6") (pinfunction "6_6") (pintype "passive"))
      (node (ref "U1") (pin "14") (pinfunction "B1/12-GCLK1_14") (pintype "bidirectional"))
    )
    (net (code "67") (name "Net-(U1-B1{slash}13)") (class "Default")
      (node (ref "FBN12") (pin "5") (pinfunction "5_5") (pintype "passive"))
      (node (ref "U1") (pin "15") (pinfunction "B1/13_15") (pintype "bidirectional"))
    )
    (net (code "68") (name "Net-(U1-B1{slash}14)") (class "Default")
      (node (ref "FBN11") (pin "7") (pinfunction "7_7") (pintype "passive"))
      (node (ref "U1") (pin "16") (pinfunction "B1/14_16") (pintype "bidirectional"))
    )
    (net (code "69") (name "Net-(U1-B1{slash}15)") (class "Default")
      (node (ref "FBN11") (pin "6") (pinfunction "6_6") (pintype "passive"))
      (node (ref "U1") (pin "17") (pinfunction "B1/15_17") (pintype "bidirectional"))
    )
    (net (code "70") (name "Net-(U1-B1{slash}16)") (class "Default")
      (node (ref "FBN11") (pin "5") (pinfunction "5_5") (pintype "passive"))
      (node (ref "U1") (pin "18") (pinfunction "B1/16_18") (pintype "bidirectional"))
    )
    (net (code "71") (name "Net-(U1-B1{slash}17)") (class "Default")
      (node (ref "FBN10") (pin "8") (pinfunction "8_8") (pintype "passive"))
      (node (ref "U1") (pin "19") (pinfunction "B1/17_19") (pintype "bidirectional"))
    )
    (net (code "72") (name "Net-(U1-B1{slash}18)") (class "Default")
      (node (ref "FBN10") (pin "7") (pinfunction "7_7") (pintype "passive"))
      (node (ref "U1") (pin "20") (pinfunction "B1/18_20") (pintype "bidirectional"))
    )
    (net (code "73") (name "Net-(U1-B1{slash}19)") (class "Default")
      (node (ref "FBN10") (pin "6") (pinfunction "6_6") (pintype "passive"))
      (node (ref "U1") (pin "21") (pinfunction "B1/19_21") (pintype "bidirectional"))
    )
    (net (code "74") (name "Net-(U1-B1{slash}20-TMS)") (class "Default")
      (node (ref "R11") (pin "2") (pinfunction "2_2") (pintype "passive"))
      (node (ref "U1") (pin "22") (pinfunction "B1/20-TMS_22") (pintype "input"))
    )
    (net (code "75") (name "Net-(U1-B1{slash}21-TDI)") (class "Default")
      (node (ref "R12") (pin "2") (pinfunction "2_2") (pintype "passive"))
      (node (ref "U1") (pin "23") (pinfunction "B1/21-TDI_23") (pintype "input"))
    )
    (net (code "76") (name "Net-(U1-B1{slash}22-TCK)") (class "Default")
      (node (ref "R10") (pin "2") (pinfunction "2_2") (pintype "passive"))
      (node (ref "U1") (pin "24") (pinfunction "B1/22-TCK_24") (pintype "input"))
    )
    (net (code "77") (name "Net-(U1-B2{slash}65)") (class "Default")
      (node (ref "J12") (pin "1") (pinfunction "1_1") (pintype "passive"))
      (node (ref "U1") (pin "66") (pinfunction "B2/65_66") (pintype "bidirectional"))
    )
    (net (code "78") (name "Net-(U1-B2{slash}90)") (class "Default")
      (node (ref "J11") (pin "3") (pinfunction "3_3") (pintype "passive"))
      (node (ref "U1") (pin "91") (pinfunction "B2/90_91") (pintype "bidirectional"))
    )
    (net (code "79") (name "Net-(U1-B2{slash}97)") (class "Default")
      (node (ref "FBN13") (pin "7") (pinfunction "7_7") (pintype "passive"))
      (node (ref "U1") (pin "98") (pinfunction "B2/97_98") (pintype "bidirectional"))
    )
    (net (code "80") (name "Net-(U1-B2{slash}98)") (class "Default")
      (node (ref "FBN13") (pin "6") (pinfunction "6_6") (pintype "passive"))
      (node (ref "U1") (pin "99") (pinfunction "B2/98_99") (pintype "bidirectional"))
    )
    (net (code "81") (name "Net-(U1-B2{slash}99)") (class "Default")
      (node (ref "FBN13") (pin "5") (pinfunction "5_5") (pintype "passive"))
      (node (ref "U1") (pin "100") (pinfunction "B2/99_100") (pintype "bidirectional"))
    )
    (net (code "82") (name "Net-(U2A-CI1)") (class "Default")
      (node (ref "R13") (pin "2") (pinfunction "2_2") (pintype "passive"))
      (node (ref "R14") (pin "2") (pinfunction "2_2") (pintype "passive"))
      (node (ref "U2") (pin "1") (pinfunction "CI1_1") (pintype "bidirectional"))
    )
    (net (code "83") (name "Net-(U2A-CI2)") (class "Default")
      (node (ref "R100") (pin "2") (pinfunction "2_2") (pintype "passive"))
      (node (ref "RN102") (pin "5") (pinfunction "5_5") (pintype "passive"))
      (node (ref "RN103") (pin "4") (pinfunction "4_4") (pintype "passive"))
      (node (ref "RN103") (pin "5") (pinfunction "5_5") (pintype "passive"))
      (node (ref "RN103") (pin "6") (pinfunction "6_6") (pintype "passive"))
      (node (ref "U2") (pin "2") (pinfunction "CI2_2") (pintype "bidirectional"))
    )
    (net (code "84") (name "Net-(U2A-CI3)") (class "Default")
      (node (ref "R110") (pin "2") (pinfunction "2_2") (pintype "passive"))
      (node (ref "RN112") (pin "8") (pinfunction "8_8") (pintype "passive"))
      (node (ref "RN113") (pin "1") (pinfunction "1_1") (pintype "passive"))
      (node (ref "RN113") (pin "7") (pinfunction "7_7") (pintype "passive"))
      (node (ref "RN113") (pin "8") (pinfunction "8_8") (pintype "passive"))
      (node (ref "U2") (pin "3") (pinfunction "CI3_3") (pintype "bidirectional"))
    )
    (net (code "85") (name "Net-(U2A-CI4)") (class "Default")
      (node (ref "R120") (pin "2") (pinfunction "2_2") (pintype "passive"))
      (node (ref "RN122") (pin "8") (pinfunction "8_8") (pintype "passive"))
      (node (ref "RN123") (pin "1") (pinfunction "1_1") (pintype "passive"))
      (node (ref "RN123") (pin "7") (pinfunction "7_7") (pintype "passive"))
      (node (ref "RN123") (pin "8") (pinfunction "8_8") (pintype "passive"))
      (node (ref "U2") (pin "4") (pinfunction "CI4_4") (pintype "bidirectional"))
    )
    (net (code "86") (name "Net-(U2A-CO1)") (class "Default")
      (node (ref "RN20") (pin "1") (pinfunction "1_1") (pintype "passive"))
      (node (ref "U2") (pin "14") (pinfunction "CO1_14") (pintype "bidirectional"))
    )
    (net (code "87") (name "Net-(U2A-CO2)") (class "Default")
      (node (ref "RN20") (pin "2") (pinfunction "2_2") (pintype "passive"))
      (node (ref "U2") (pin "13") (pinfunction "CO2_13") (pintype "bidirectional"))
    )
    (net (code "88") (name "Net-(U2A-CO3)") (class "Default")
      (node (ref "RN20") (pin "3") (pinfunction "3_3") (pintype "passive"))
      (node (ref "U2") (pin "12") (pinfunction "CO3_12") (pintype "bidirectional"))
    )
    (net (code "89") (name "Net-(U2A-CO4)") (class "Default")
      (node (ref "RN20") (pin "4") (pinfunction "4_4") (pintype "passive"))
      (node (ref "U2") (pin "11") (pinfunction "CO4_11") (pintype "bidirectional"))
    )
    (net (code "90") (name "VCC@1.8V") (class "Default")
      (node (ref "C10") (pin "1") (pinfunction "1_1") (pintype "passive"))
      (node (ref "C11") (pin "1") (pinfunction "1_1") (pintype "passive"))
      (node (ref "C12") (pin "1") (pinfunction "1_1") (pintype "passive"))
      (node (ref "C13") (pin "1") (pinfunction "1_1") (pintype "passive"))
      (node (ref "C33") (pin "1") (pinfunction "1_1") (pintype "passive"))
      (node (ref "J1") (pin "2") (pinfunction "2_2") (pintype "passive"))
      (node (ref "U1") (pin "13") (pinfunction "VCCINT_13") (pintype "power_in"))
      (node (ref "U1") (pin "39") (pinfunction "VCCINT_39") (pintype "power_in"))
      (node (ref "U1") (pin "63") (pinfunction "VCCINT_63") (pintype "power_in"))
      (node (ref "U1") (pin "88") (pinfunction "VCCINT_88") (pintype "power_in"))
      (node (ref "U3") (pin "5") (pinfunction "OUT_5") (pintype "passive"))
    )
    (net (code "91") (name "VCC@3.3V") (class "Default")
      (node (ref "C14") (pin "1") (pinfunction "1_1") (pintype "passive"))
      (node (ref "C15") (pin "1") (pinfunction "1_1") (pintype "passive"))
      (node (ref "C16") (pin "1") (pinfunction "1_1") (pintype "passive"))
      (node (ref "C17") (pin "1") (pinfunction "1_1") (pintype "passive"))
      (node (ref "C18") (pin "1") (pinfunction "1_1") (pintype "passive"))
      (node (ref "C19") (pin "1") (pinfunction "1_1") (pintype "passive"))
      (node (ref "C21") (pin "1") (pinfunction "1_1") (pintype "passive"))
      (node (ref "C22") (pin "1") (pinfunction "1_1") (pintype "passive"))
      (node (ref "C31") (pin "1") (pinfunction "1_1") (pintype "passive"))
      (node (ref "C32") (pin "1") (pinfunction "1_1") (pintype "passive"))
      (node (ref "FB1") (pin "2") (pinfunction "2_2") (pintype "passive"))
      (node (ref "J1") (pin "1") (pinfunction "1_1") (pintype "passive"))
      (node (ref "L1") (pin "2") (pinfunction "2_2") (pintype "passive"))
      (node (ref "R11") (pin "1") (pinfunction "1_1") (pintype "passive"))
      (node (ref "R12") (pin "1") (pinfunction "1_1") (pintype "passive"))
      (node (ref "U1") (pin "31") (pinfunction "VCCIO_31") (pintype "power_in"))
      (node (ref "U1") (pin "45") (pinfunction "VCCIO_45") (pintype "power_in"))
      (node (ref "U1") (pin "59") (pinfunction "VCCIO_59") (pintype "power_in"))
      (node (ref "U1") (pin "80") (pinfunction "VCCIO_80") (pintype "power_in"))
      (node (ref "U1") (pin "9") (pinfunction "VCCIO_9") (pintype "power_in"))
      (node (ref "U1") (pin "94") (pinfunction "VCCIO_94") (pintype "power_in"))
      (node (ref "U2") (pin "10") (pinfunction "VCC_10") (pintype "bidirectional"))
      (node (ref "U3") (pin "1") (pinfunction "IN_1") (pintype "input"))
      (node (ref "U3") (pin "3") (pinfunction "~{EN}_3") (pintype "input"))
    )
    (net (code "92") (name "unconnected-(FBN10-Pad4)") (class "Default")
      (node (ref "FBN10") (pin "4") (pinfunction "4_4") (pintype "passive"))
    )
    (net (code "93") (name "unconnected-(FBN10-Pad5)") (class "Default")
      (node (ref "FBN10") (pin "5") (pinfunction "5_5") (pintype "passive"))
    )
    (net (code "94") (name "unconnected-(FBN11-Pad1)") (class "Default")
      (node (ref "FBN11") (pin "1") (pinfunction "1_1") (pintype "passive"))
    )
    (net (code "95") (name "unconnected-(FBN11-Pad8)") (class "Default")
      (node (ref "FBN11") (pin "8") (pinfunction "8_8") (pintype "passive"))
    )
    (net (code "96") (name "unconnected-(FBN12-Pad1)") (class "Default")
      (node (ref "FBN12") (pin "1") (pinfunction "1_1") (pintype "passive"))
    )
    (net (code "97") (name "unconnected-(FBN12-Pad8)") (class "Default")
      (node (ref "FBN12") (pin "8") (pinfunction "8_8") (pintype "passive"))
    )
    (net (code "98") (name "unconnected-(FBN13-Pad1)") (class "Default")
      (node (ref "FBN13") (pin "1") (pinfunction "1_1") (pintype "passive"))
    )
    (net (code "99") (name "unconnected-(FBN13-Pad8)") (class "Default")
      (node (ref "FBN13") (pin "8") (pinfunction "8_8") (pintype "passive"))
    )
    (net (code "100") (name "unconnected-(RN101-Pad1)") (class "Default")
      (node (ref "RN101") (pin "1") (pinfunction "1_1") (pintype "passive"))
    )
    (net (code "101") (name "unconnected-(RN101-Pad8)") (class "Default")
      (node (ref "RN101") (pin "8") (pinfunction "8_8") (pintype "passive"))
    )
    (net (code "102") (name "unconnected-(RN111-Pad4)") (class "Default")
      (node (ref "RN111") (pin "4") (pinfunction "4_4") (pintype "passive"))
    )
    (net (code "103") (name "unconnected-(RN111-Pad5)") (class "Default")
      (node (ref "RN111") (pin "5") (pinfunction "5_5") (pintype "passive"))
    )
    (net (code "104") (name "unconnected-(RN121-Pad4)") (class "Default")
      (node (ref "RN121") (pin "4") (pinfunction "4_4") (pintype "passive"))
    )
    (net (code "105") (name "unconnected-(RN121-Pad5)") (class "Default")
      (node (ref "RN121") (pin "5") (pinfunction "5_5") (pintype "passive"))
    )
    (net (code "106") (name "unconnected-(U1-B1{slash}1-Pad3)") (class "Default")
      (node (ref "U1") (pin "3") (pinfunction "B1/1_3") (pintype "bidirectional"))
    )
    (net (code "107") (name "unconnected-(U1-B1{slash}2-Pad4)") (class "Default")
      (node (ref "U1") (pin "4") (pinfunction "B1/2_4") (pintype "bidirectional"))
    )
    (net (code "108") (name "unconnected-(U1-B1{slash}3-Pad5)") (class "Default")
      (node (ref "U1") (pin "5") (pinfunction "B1/3_5") (pintype "bidirectional"))
    )
    (net (code "109") (name "unconnected-(U1-B1{slash}4-Pad6)") (class "Default")
      (node (ref "U1") (pin "6") (pinfunction "B1/4_6") (pintype "bidirectional"))
    )
    (net (code "110") (name "unconnected-(U1-B1{slash}5-Pad7)") (class "Default")
      (node (ref "U1") (pin "7") (pinfunction "B1/5_7") (pintype "bidirectional"))
    )
    (net (code "111") (name "unconnected-(U1-B1{slash}24-TDO-Pad25)") (class "Default")
      (node (ref "U1") (pin "25") (pinfunction "B1/24-TDO_25") (pintype "output"))
    )
    (net (code "112") (name "unconnected-(U1-B1{slash}34-Pad35)") (class "Default")
      (node (ref "U1") (pin "35") (pinfunction "B1/34_35") (pintype "bidirectional"))
    )
    (net (code "113") (name "unconnected-(U1-B1{slash}35-Pad36)") (class "Default")
      (node (ref "U1") (pin "36") (pinfunction "B1/35_36") (pintype "bidirectional"))
    )
    (net (code "114") (name "unconnected-(U1-B1{slash}37-Pad38)") (class "Default")
      (node (ref "U1") (pin "38") (pinfunction "B1/37_38") (pintype "bidirectional"))
    )
    (net (code "115") (name "unconnected-(U1-B1{slash}39-Pad40)") (class "Default")
      (node (ref "U1") (pin "40") (pinfunction "B1/39_40") (pintype "bidirectional"))
    )
    (net (code "116") (name "unconnected-(U1-B1{slash}40-Pad41)") (class "Default")
      (node (ref "U1") (pin "41") (pinfunction "B1/40_41") (pintype "bidirectional"))
    )
    (net (code "117") (name "unconnected-(U1-B1{slash}41-Pad42)") (class "Default")
      (node (ref "U1") (pin "42") (pinfunction "B1/41_42") (pintype "bidirectional"))
    )
    (net (code "118") (name "unconnected-(U1-B2{slash}51-Pad52)") (class "Default")
      (node (ref "U1") (pin "52") (pinfunction "B2/51_52") (pintype "bidirectional"))
    )
    (net (code "119") (name "unconnected-(U1-B2{slash}53-Pad54)") (class "Default")
      (node (ref "U1") (pin "54") (pinfunction "B2/53_54") (pintype "bidirectional"))
    )
    (net (code "120") (name "unconnected-(U1-B2{slash}54-Pad55)") (class "Default")
      (node (ref "U1") (pin "55") (pinfunction "B2/54_55") (pintype "bidirectional"))
    )
    (net (code "121") (name "unconnected-(U1-B2{slash}55-Pad56)") (class "Default")
      (node (ref "U1") (pin "56") (pinfunction "B2/55_56") (pintype "bidirectional"))
    )
    (net (code "122") (name "unconnected-(U1-B2{slash}56-Pad57)") (class "Default")
      (node (ref "U1") (pin "57") (pinfunction "B2/56_57") (pintype "bidirectional"))
    )
    (net (code "123") (name "unconnected-(U1-B2{slash}57-Pad58)") (class "Default")
      (node (ref "U1") (pin "58") (pinfunction "B2/57_58") (pintype "bidirectional"))
    )
    (net (code "124") (name "unconnected-(U1-B2{slash}60-Pad61)") (class "Default")
      (node (ref "U1") (pin "61") (pinfunction "B2/60_61") (pintype "bidirectional"))
    )
    (net (code "125") (name "unconnected-(U1-B2{slash}61-GCLK2-Pad62)") (class "Default")
      (node (ref "U1") (pin "62") (pinfunction "B2/61-GCLK2_62") (pintype "bidirectional"))
    )
    (net (code "126") (name "unconnected-(U1-B2{slash}63-GCLK3-Pad64)") (class "Default")
      (node (ref "U1") (pin "64") (pinfunction "B2/63-GCLK3_64") (pintype "bidirectional"))
    )
    (net (code "127") (name "unconnected-(U1-B2{slash}66-Pad67)") (class "Default")
      (node (ref "U1") (pin "67") (pinfunction "B2/66_67") (pintype "bidirectional"))
    )
    (net (code "128") (name "unconnected-(U1-B2{slash}80-Pad81)") (class "Default")
      (node (ref "U1") (pin "81") (pinfunction "B2/80_81") (pintype "bidirectional"))
    )
    (net (code "129") (name "unconnected-(U1-B2{slash}81-Pad82)") (class "Default")
      (node (ref "U1") (pin "82") (pinfunction "B2/81_82") (pintype "bidirectional"))
    )
    (net (code "130") (name "unconnected-(U1-B2{slash}82-Pad83)") (class "Default")
      (node (ref "U1") (pin "83") (pinfunction "B2/82_83") (pintype "bidirectional"))
    )
    (net (code "131") (name "unconnected-(U1-B2{slash}83-Pad84)") (class "Default")
      (node (ref "U1") (pin "84") (pinfunction "B2/83_84") (pintype "bidirectional"))
    )
    (net (code "132") (name "unconnected-(U1-B2{slash}84-Pad85)") (class "Default")
      (node (ref "U1") (pin "85") (pinfunction "B2/84_85") (pintype "bidirectional"))
    )
    (net (code "133") (name "unconnected-(U1-B2{slash}85-Pad86)") (class "Default")
      (node (ref "U1") (pin "86") (pinfunction "B2/85_86") (pintype "bidirectional"))
    )
    (net (code "134") (name "unconnected-(U1-B2{slash}86-Pad87)") (class "Default")
      (node (ref "U1") (pin "87") (pinfunction "B2/86_87") (pintype "bidirectional"))
    )
    (net (code "135") (name "unconnected-(U1-B2{slash}88-Pad89)") (class "Default")
      (node (ref "U1") (pin "89") (pinfunction "B2/88_89") (pintype "bidirectional"))
    )
    (net (code "136") (name "unconnected-(U1-B2{slash}91-Pad92)") (class "Default")
      (node (ref "U1") (pin "92") (pinfunction "B2/91_92") (pintype "bidirectional"))
    )
    (net (code "137") (name "unconnected-(U1-B2{slash}95-Pad96)") (class "Default")
      (node (ref "U1") (pin "96") (pinfunction "B2/95_96") (pintype "bidirectional"))
    )
    (net (code "138") (name "unconnected-(U1-B2{slash}96-Pad97)") (class "Default")
      (node (ref "U1") (pin "97") (pinfunction "B2/96_97") (pintype "bidirectional"))
    )
    (net (code "139") (name "unconnected-(U3-NC{slash}FB-Pad4)") (class "Default")
      (node (ref "U3") (pin "4") (pinfunction "NC/FB_4") (pintype "passive"))
    )
  )
)
